# IDC_EXT_Connectors.net
KiCad netlist of a schematic drawn in Altium Designer
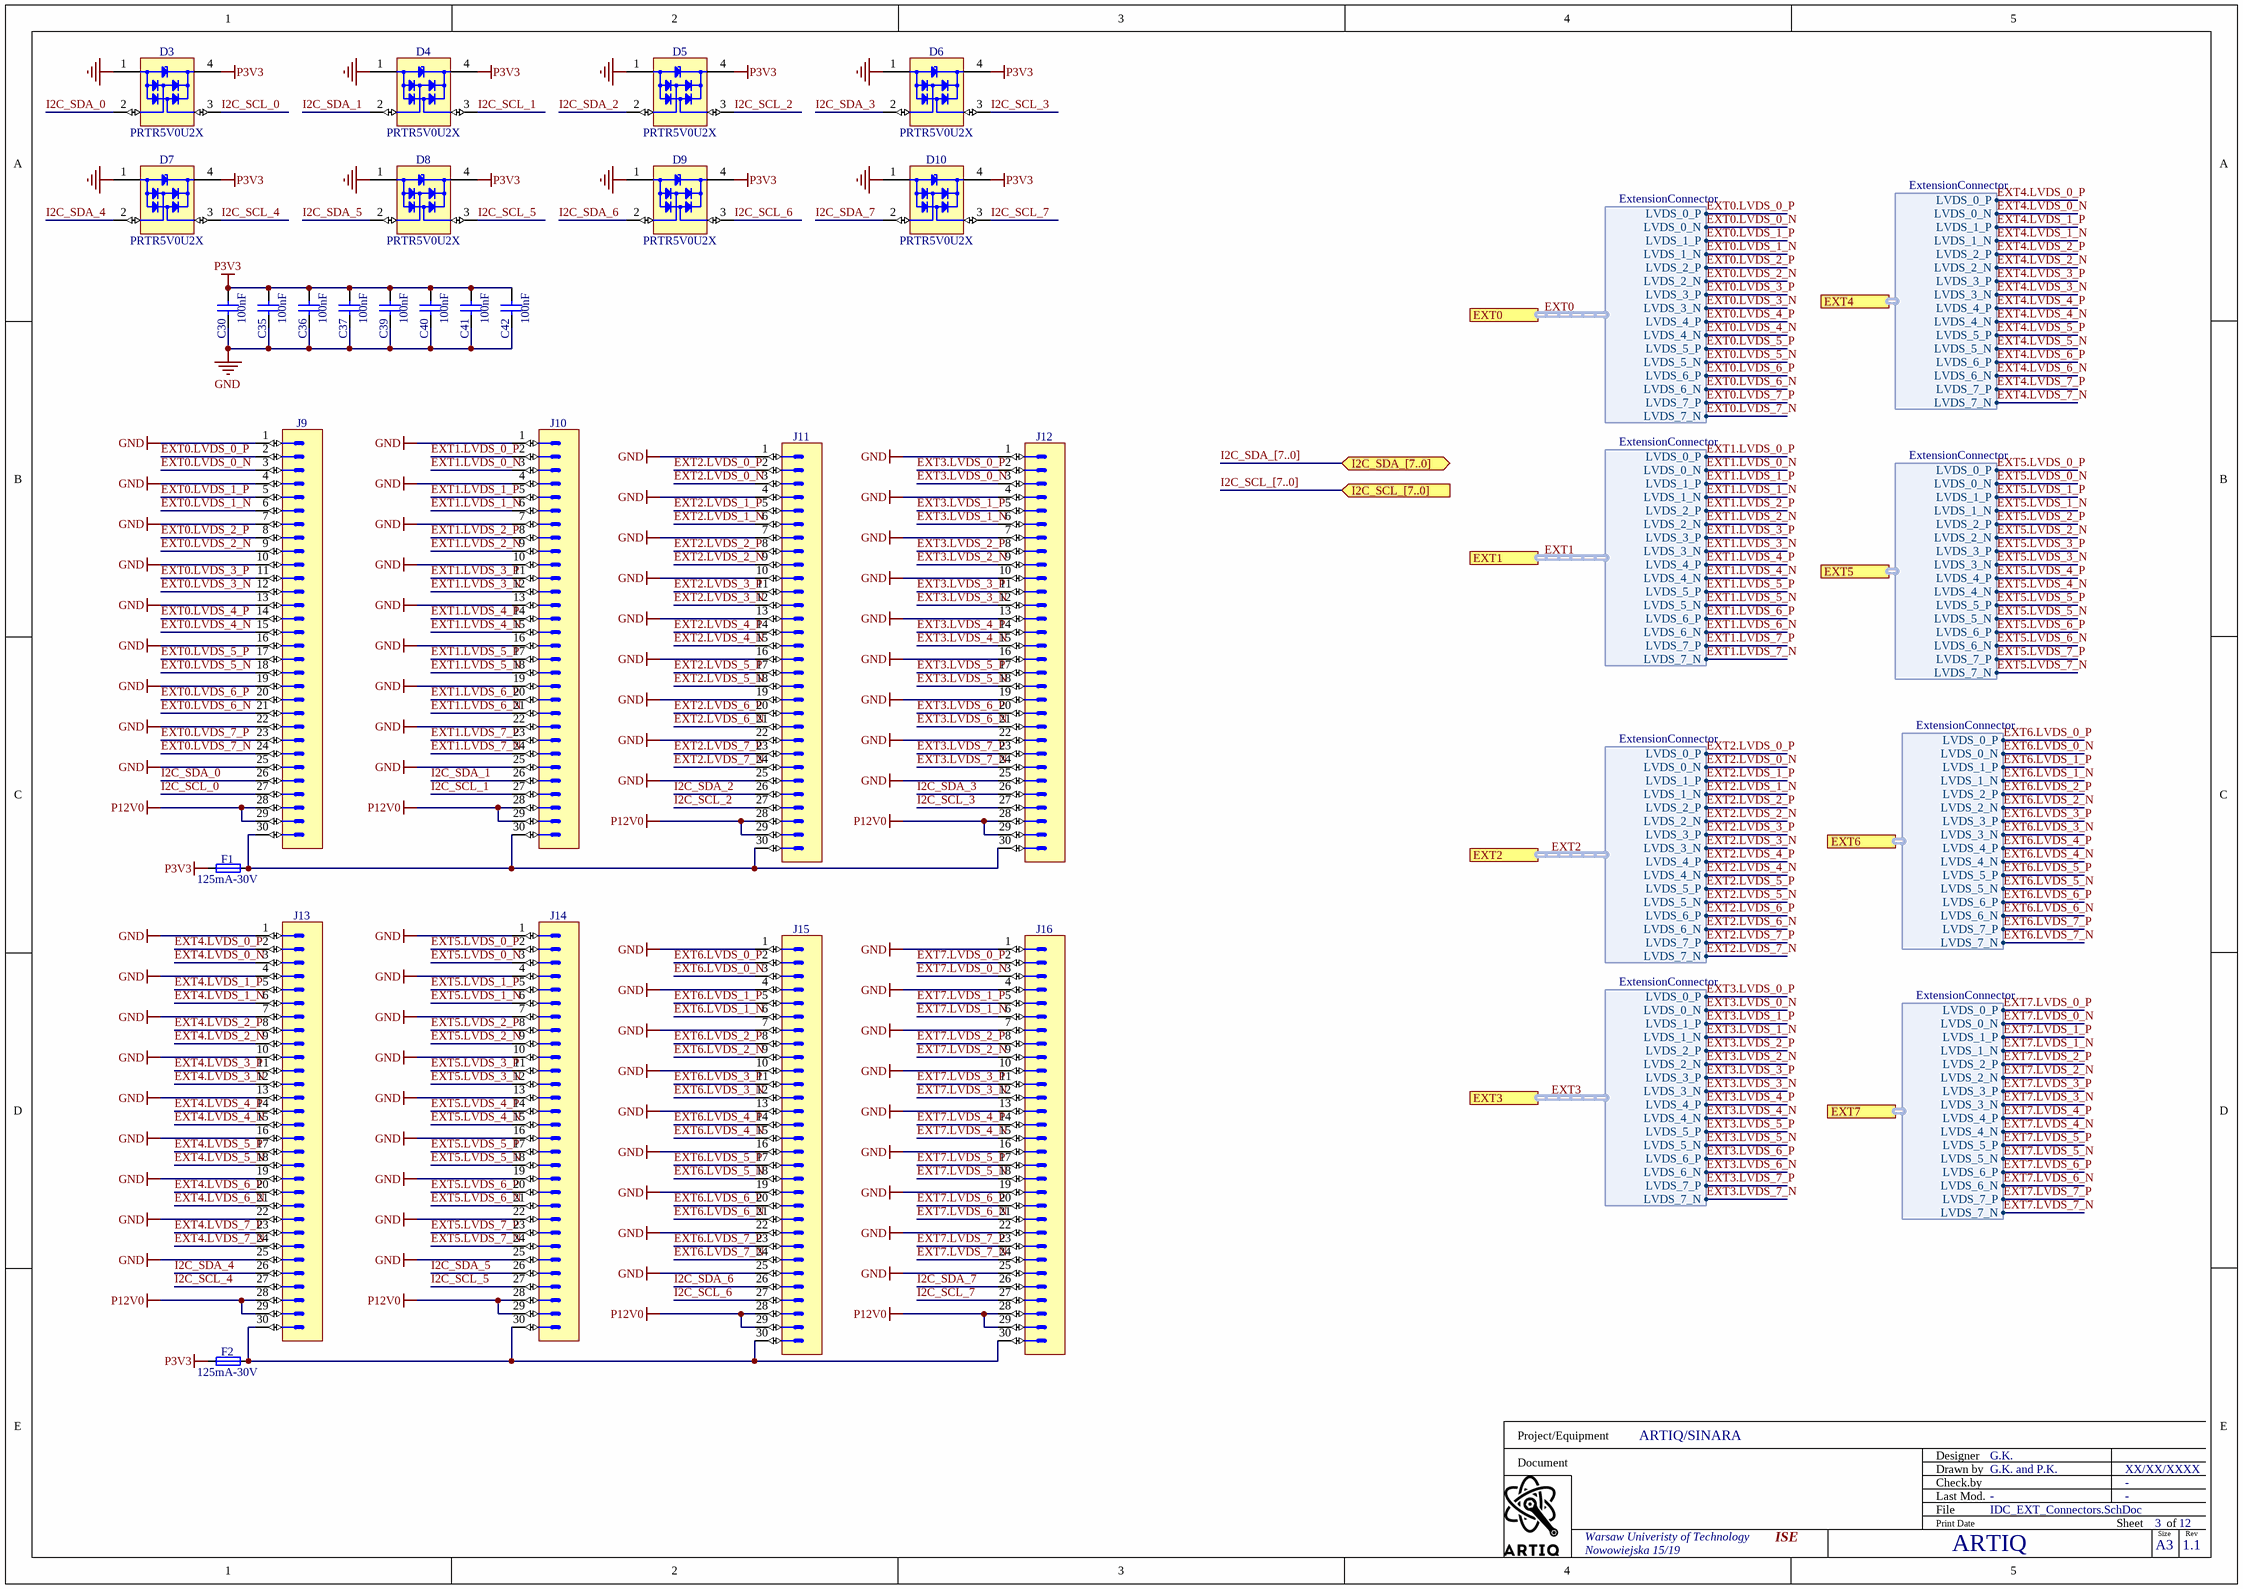
[diagram p0: IDC_EXT_Connectors.SchDoc]

(export (version "E")
  (design (tool "Eeschema 10.0.6"))
  (components
    (comp (ref "C30")
      (value "100nF")
      (footprint "CAPC0603X33N")
      (description "Non-polarised capacitor")
      (fields
        (field (name "PART NUMBER") "CC0201_100NF_6.3V_10%_X5R")
        (field (name "VOLTAGE") "6.3V")
        (field (name "AUTHOR") "CERN DEM JLC")
      )
      (libsource (lib "Capacitors") (part "Capacitor - non polarized"))
    )
    (comp (ref "C35")
      (value "100nF")
      (footprint "CAPC0603X33N")
      (description "Non-polarised capacitor")
      (fields
        (field (name "PART NUMBER") "CC0201_100NF_6.3V_10%_X5R")
        (field (name "VOLTAGE") "6.3V")
        (field (name "AUTHOR") "CERN DEM JLC")
      )
      (libsource (lib "Capacitors") (part "Capacitor - non polarized"))
    )
    (comp (ref "C36")
      (value "100nF")
      (footprint "CAPC0603X33N")
      (description "Non-polarised capacitor")
      (fields
        (field (name "PART NUMBER") "CC0201_100NF_6.3V_10%_X5R")
        (field (name "VOLTAGE") "6.3V")
        (field (name "AUTHOR") "CERN DEM JLC")
      )
      (libsource (lib "Capacitors") (part "Capacitor - non polarized"))
    )
    (comp (ref "C37")
      (value "100nF")
      (footprint "CAPC0603X33N")
      (description "Non-polarised capacitor")
      (fields
        (field (name "PART NUMBER") "CC0201_100NF_6.3V_10%_X5R")
        (field (name "VOLTAGE") "6.3V")
        (field (name "AUTHOR") "CERN DEM JLC")
      )
      (libsource (lib "Capacitors") (part "Capacitor - non polarized"))
    )
    (comp (ref "C39")
      (value "100nF")
      (footprint "CAPC0603X33N")
      (description "Non-polarised capacitor")
      (fields
        (field (name "PART NUMBER") "CC0201_100NF_6.3V_10%_X5R")
        (field (name "VOLTAGE") "6.3V")
        (field (name "AUTHOR") "CERN DEM JLC")
      )
      (libsource (lib "Capacitors") (part "Capacitor - non polarized"))
    )
    (comp (ref "C40")
      (value "100nF")
      (footprint "CAPC0603X33N")
      (description "Non-polarised capacitor")
      (fields
        (field (name "PART NUMBER") "CC0201_100NF_6.3V_10%_X5R")
        (field (name "VOLTAGE") "6.3V")
        (field (name "AUTHOR") "CERN DEM JLC")
      )
      (libsource (lib "Capacitors") (part "Capacitor - non polarized"))
    )
    (comp (ref "C41")
      (value "100nF")
      (footprint "CAPC0603X33N")
      (description "Non-polarised capacitor")
      (fields
        (field (name "PART NUMBER") "CC0201_100NF_6.3V_10%_X5R")
        (field (name "VOLTAGE") "6.3V")
        (field (name "AUTHOR") "CERN DEM JLC")
      )
      (libsource (lib "Capacitors") (part "Capacitor - non polarized"))
    )
    (comp (ref "C42")
      (value "100nF")
      (footprint "CAPC0603X33N")
      (description "Non-polarised capacitor")
      (fields
        (field (name "PART NUMBER") "CC0201_100NF_6.3V_10%_X5R")
        (field (name "VOLTAGE") "6.3V")
        (field (name "AUTHOR") "CERN DEM JLC")
      )
      (libsource (lib "Capacitors") (part "Capacitor - non polarized"))
    )
    (comp (ref "D3")
      (value "PRTR5V0U2X")
      (footprint "SOT190P230X110-4N")
      (description "Ultra Low Capacitance Double Rail-to-Rail ESD Protection Diode")
      (fields
        (field (name "VOLTAGE") "5.5V")
        (field (name "MANUFACTURER") "NXP SEMICONDUCTORS")
        (field (name "AUTHOR") "CERN DEM JLC")
      )
      (libsource (lib "ICs And Semiconductors") (part "PRTR5V0U2X"))
    )
    (comp (ref "D4")
      (value "PRTR5V0U2X")
      (footprint "SOT190P230X110-4N")
      (description "Ultra Low Capacitance Double Rail-to-Rail ESD Protection Diode")
      (fields
        (field (name "VOLTAGE") "5.5V")
        (field (name "MANUFACTURER") "NXP SEMICONDUCTORS")
        (field (name "AUTHOR") "CERN DEM JLC")
      )
      (libsource (lib "ICs And Semiconductors") (part "PRTR5V0U2X"))
    )
    (comp (ref "D5")
      (value "PRTR5V0U2X")
      (footprint "SOT190P230X110-4N")
      (description "Ultra Low Capacitance Double Rail-to-Rail ESD Protection Diode")
      (fields
        (field (name "VOLTAGE") "5.5V")
        (field (name "MANUFACTURER") "NXP SEMICONDUCTORS")
        (field (name "AUTHOR") "CERN DEM JLC")
      )
      (libsource (lib "ICs And Semiconductors") (part "PRTR5V0U2X"))
    )
    (comp (ref "D6")
      (value "PRTR5V0U2X")
      (footprint "SOT190P230X110-4N")
      (description "Ultra Low Capacitance Double Rail-to-Rail ESD Protection Diode")
      (fields
        (field (name "VOLTAGE") "5.5V")
        (field (name "MANUFACTURER") "NXP SEMICONDUCTORS")
        (field (name "AUTHOR") "CERN DEM JLC")
      )
      (libsource (lib "ICs And Semiconductors") (part "PRTR5V0U2X"))
    )
    (comp (ref "D7")
      (value "PRTR5V0U2X")
      (footprint "SOT190P230X110-4N")
      (description "Ultra Low Capacitance Double Rail-to-Rail ESD Protection Diode")
      (fields
        (field (name "VOLTAGE") "5.5V")
        (field (name "MANUFACTURER") "NXP SEMICONDUCTORS")
        (field (name "AUTHOR") "CERN DEM JLC")
      )
      (libsource (lib "ICs And Semiconductors") (part "PRTR5V0U2X"))
    )
    (comp (ref "D8")
      (value "PRTR5V0U2X")
      (footprint "SOT190P230X110-4N")
      (description "Ultra Low Capacitance Double Rail-to-Rail ESD Protection Diode")
      (fields
        (field (name "VOLTAGE") "5.5V")
        (field (name "MANUFACTURER") "NXP SEMICONDUCTORS")
        (field (name "AUTHOR") "CERN DEM JLC")
      )
      (libsource (lib "ICs And Semiconductors") (part "PRTR5V0U2X"))
    )
    (comp (ref "D9")
      (value "PRTR5V0U2X")
      (footprint "SOT190P230X110-4N")
      (description "Ultra Low Capacitance Double Rail-to-Rail ESD Protection Diode")
      (fields
        (field (name "VOLTAGE") "5.5V")
        (field (name "MANUFACTURER") "NXP SEMICONDUCTORS")
        (field (name "AUTHOR") "CERN DEM JLC")
      )
      (libsource (lib "ICs And Semiconductors") (part "PRTR5V0U2X"))
    )
    (comp (ref "D10")
      (value "PRTR5V0U2X")
      (footprint "SOT190P230X110-4N")
      (description "Ultra Low Capacitance Double Rail-to-Rail ESD Protection Diode")
      (fields
        (field (name "VOLTAGE") "5.5V")
        (field (name "MANUFACTURER") "NXP SEMICONDUCTORS")
        (field (name "AUTHOR") "CERN DEM JLC")
      )
      (libsource (lib "ICs And Semiconductors") (part "PRTR5V0U2X"))
    )
    (comp (ref "F1")
      (value "125mA-30V")
      (footprint "FUSR_LITTELFUSE_1206L012")
      (description "Fuse")
      (fields
        (field (name "PART NUMBER") "FUSR_LITTELFUSE_1206L012")
        (field (name "MANUFACTURER") "LITTELFUSE")
        (field (name "AUTHOR") "CERN DEM JLC")
      )
      (libsource (lib "Eletro-mechanical") (part "Fuse"))
    )
    (comp (ref "F2")
      (value "125mA-30V")
      (footprint "FUSR_LITTELFUSE_1206L012")
      (description "Fuse")
      (fields
        (field (name "PART NUMBER") "FUSR_LITTELFUSE_1206L012")
        (field (name "MANUFACTURER") "LITTELFUSE")
        (field (name "AUTHOR") "CERN DEM JLC")
      )
      (libsource (lib "Eletro-mechanical") (part "Fuse"))
    )
    (comp (ref "J9")
      (value "~")
      (footprint "3M_N2530-6002RB")
      (description "Connector 30 Male")
      (fields
        (field (name "PART NUMBER") "3M_N2530-6002RB")
        (field (name "MANUFACTURER") "3M")
        (field (name "AUTHOR") "CERN DEM JLC")
      )
      (libsource (lib "Connectors") (part "Connector 30 Male"))
    )
    (comp (ref "J10")
      (value "~")
      (footprint "3M_N2530-6002RB")
      (description "Connector 30 Male")
      (fields
        (field (name "PART NUMBER") "3M_N2530-6002RB")
        (field (name "MANUFACTURER") "3M")
        (field (name "AUTHOR") "CERN DEM JLC")
      )
      (libsource (lib "Connectors") (part "Connector 30 Male"))
    )
    (comp (ref "J11")
      (value "~")
      (footprint "3M_N2530-6002RB")
      (description "Connector 30 Male")
      (fields
        (field (name "PART NUMBER") "3M_N2530-6002RB")
        (field (name "MANUFACTURER") "3M")
        (field (name "AUTHOR") "CERN DEM JLC")
      )
      (libsource (lib "Connectors") (part "Connector 30 Male"))
    )
    (comp (ref "J12")
      (value "~")
      (footprint "3M_N2530-6002RB")
      (description "Connector 30 Male")
      (fields
        (field (name "PART NUMBER") "3M_N2530-6002RB")
        (field (name "MANUFACTURER") "3M")
        (field (name "AUTHOR") "CERN DEM JLC")
      )
      (libsource (lib "Connectors") (part "Connector 30 Male"))
    )
    (comp (ref "J13")
      (value "~")
      (footprint "3M_N2530-6002RB")
      (description "Connector 30 Male")
      (fields
        (field (name "PART NUMBER") "3M_N2530-6002RB")
        (field (name "MANUFACTURER") "3M")
        (field (name "AUTHOR") "CERN DEM JLC")
      )
      (libsource (lib "Connectors") (part "Connector 30 Male"))
    )
    (comp (ref "J14")
      (value "~")
      (footprint "3M_N2530-6002RB")
      (description "Connector 30 Male")
      (fields
        (field (name "PART NUMBER") "3M_N2530-6002RB")
        (field (name "MANUFACTURER") "3M")
        (field (name "AUTHOR") "CERN DEM JLC")
      )
      (libsource (lib "Connectors") (part "Connector 30 Male"))
    )
    (comp (ref "J15")
      (value "~")
      (footprint "3M_N2530-6002RB")
      (description "Connector 30 Male")
      (fields
        (field (name "PART NUMBER") "3M_N2530-6002RB")
        (field (name "MANUFACTURER") "3M")
        (field (name "AUTHOR") "CERN DEM JLC")
      )
      (libsource (lib "Connectors") (part "Connector 30 Male"))
    )
    (comp (ref "J16")
      (value "~")
      (footprint "3M_N2530-6002RB")
      (description "Connector 30 Male")
      (fields
        (field (name "PART NUMBER") "3M_N2530-6002RB")
        (field (name "MANUFACTURER") "3M")
        (field (name "AUTHOR") "CERN DEM JLC")
      )
      (libsource (lib "Connectors") (part "Connector 30 Male"))
    )
  )
  (nets
    (net (code "6") (name "/EXT0.LVDS_0_N") (class "Default")
      (node (ref "J9") (pin "3") (pinfunction "3_3") (pintype "bidirectional"))
    )
    (net (code "7") (name "/EXT0.LVDS_0_P") (class "Default")
      (node (ref "J9") (pin "2") (pinfunction "2_2") (pintype "bidirectional"))
    )
    (net (code "8") (name "/EXT0.LVDS_1_N") (class "Default")
      (node (ref "J9") (pin "6") (pinfunction "6_6") (pintype "bidirectional"))
    )
    (net (code "9") (name "/EXT0.LVDS_1_P") (class "Default")
      (node (ref "J9") (pin "5") (pinfunction "5_5") (pintype "bidirectional"))
    )
    (net (code "10") (name "/EXT0.LVDS_2_N") (class "Default")
      (node (ref "J9") (pin "9") (pinfunction "9_9") (pintype "bidirectional"))
    )
    (net (code "11") (name "/EXT0.LVDS_2_P") (class "Default")
      (node (ref "J9") (pin "8") (pinfunction "8_8") (pintype "bidirectional"))
    )
    (net (code "12") (name "/EXT0.LVDS_3_N") (class "Default")
      (node (ref "J9") (pin "12") (pinfunction "12_12") (pintype "bidirectional"))
    )
    (net (code "13") (name "/EXT0.LVDS_3_P") (class "Default")
      (node (ref "J9") (pin "11") (pinfunction "11_11") (pintype "bidirectional"))
    )
    (net (code "14") (name "/EXT0.LVDS_4_N") (class "Default")
      (node (ref "J9") (pin "15") (pinfunction "15_15") (pintype "bidirectional"))
    )
    (net (code "15") (name "/EXT0.LVDS_4_P") (class "Default")
      (node (ref "J9") (pin "14") (pinfunction "14_14") (pintype "bidirectional"))
    )
    (net (code "16") (name "/EXT0.LVDS_5_N") (class "Default")
      (node (ref "J9") (pin "18") (pinfunction "18_18") (pintype "bidirectional"))
    )
    (net (code "17") (name "/EXT0.LVDS_5_P") (class "Default")
      (node (ref "J9") (pin "17") (pinfunction "17_17") (pintype "bidirectional"))
    )
    (net (code "18") (name "/EXT0.LVDS_6_N") (class "Default")
      (node (ref "J9") (pin "21") (pinfunction "21_21") (pintype "bidirectional"))
    )
    (net (code "19") (name "/EXT0.LVDS_6_P") (class "Default")
      (node (ref "J9") (pin "20") (pinfunction "20_20") (pintype "bidirectional"))
    )
    (net (code "20") (name "/EXT0.LVDS_7_N") (class "Default")
      (node (ref "J9") (pin "24") (pinfunction "24_24") (pintype "bidirectional"))
    )
    (net (code "21") (name "/EXT0.LVDS_7_P") (class "Default")
      (node (ref "J9") (pin "23") (pinfunction "23_23") (pintype "bidirectional"))
    )
    (net (code "23") (name "/EXT1.LVDS_0_N") (class "Default")
      (node (ref "J10") (pin "3") (pinfunction "3_3") (pintype "bidirectional"))
    )
    (net (code "24") (name "/EXT1.LVDS_0_P") (class "Default")
      (node (ref "J10") (pin "2") (pinfunction "2_2") (pintype "bidirectional"))
    )
    (net (code "25") (name "/EXT1.LVDS_1_N") (class "Default")
      (node (ref "J10") (pin "6") (pinfunction "6_6") (pintype "bidirectional"))
    )
    (net (code "26") (name "/EXT1.LVDS_1_P") (class "Default")
      (node (ref "J10") (pin "5") (pinfunction "5_5") (pintype "bidirectional"))
    )
    (net (code "27") (name "/EXT1.LVDS_2_N") (class "Default")
      (node (ref "J10") (pin "9") (pinfunction "9_9") (pintype "bidirectional"))
    )
    (net (code "28") (name "/EXT1.LVDS_2_P") (class "Default")
      (node (ref "J10") (pin "8") (pinfunction "8_8") (pintype "bidirectional"))
    )
    (net (code "29") (name "/EXT1.LVDS_3_N") (class "Default")
      (node (ref "J10") (pin "12") (pinfunction "12_12") (pintype "bidirectional"))
    )
    (net (code "30") (name "/EXT1.LVDS_3_P") (class "Default")
      (node (ref "J10") (pin "11") (pinfunction "11_11") (pintype "bidirectional"))
    )
    (net (code "31") (name "/EXT1.LVDS_4_N") (class "Default")
      (node (ref "J10") (pin "15") (pinfunction "15_15") (pintype "bidirectional"))
    )
    (net (code "32") (name "/EXT1.LVDS_4_P") (class "Default")
      (node (ref "J10") (pin "14") (pinfunction "14_14") (pintype "bidirectional"))
    )
    (net (code "33") (name "/EXT1.LVDS_5_N") (class "Default")
      (node (ref "J10") (pin "18") (pinfunction "18_18") (pintype "bidirectional"))
    )
    (net (code "34") (name "/EXT1.LVDS_5_P") (class "Default")
      (node (ref "J10") (pin "17") (pinfunction "17_17") (pintype "bidirectional"))
    )
    (net (code "35") (name "/EXT1.LVDS_6_N") (class "Default")
      (node (ref "J10") (pin "21") (pinfunction "21_21") (pintype "bidirectional"))
    )
    (net (code "36") (name "/EXT1.LVDS_6_P") (class "Default")
      (node (ref "J10") (pin "20") (pinfunction "20_20") (pintype "bidirectional"))
    )
    (net (code "37") (name "/EXT1.LVDS_7_N") (class "Default")
      (node (ref "J10") (pin "24") (pinfunction "24_24") (pintype "bidirectional"))
    )
    (net (code "38") (name "/EXT1.LVDS_7_P") (class "Default")
      (node (ref "J10") (pin "23") (pinfunction "23_23") (pintype "bidirectional"))
    )
    (net (code "40") (name "/EXT2.LVDS_0_N") (class "Default")
      (node (ref "J11") (pin "3") (pinfunction "3_3") (pintype "bidirectional"))
    )
    (net (code "41") (name "/EXT2.LVDS_0_P") (class "Default")
      (node (ref "J11") (pin "2") (pinfunction "2_2") (pintype "bidirectional"))
    )
    (net (code "42") (name "/EXT2.LVDS_1_N") (class "Default")
      (node (ref "J11") (pin "6") (pinfunction "6_6") (pintype "bidirectional"))
    )
    (net (code "43") (name "/EXT2.LVDS_1_P") (class "Default")
      (node (ref "J11") (pin "5") (pinfunction "5_5") (pintype "bidirectional"))
    )
    (net (code "44") (name "/EXT2.LVDS_2_N") (class "Default")
      (node (ref "J11") (pin "9") (pinfunction "9_9") (pintype "bidirectional"))
    )
    (net (code "45") (name "/EXT2.LVDS_2_P") (class "Default")
      (node (ref "J11") (pin "8") (pinfunction "8_8") (pintype "bidirectional"))
    )
    (net (code "46") (name "/EXT2.LVDS_3_N") (class "Default")
      (node (ref "J11") (pin "12") (pinfunction "12_12") (pintype "bidirectional"))
    )
    (net (code "47") (name "/EXT2.LVDS_3_P") (class "Default")
      (node (ref "J11") (pin "11") (pinfunction "11_11") (pintype "bidirectional"))
    )
    (net (code "48") (name "/EXT2.LVDS_4_N") (class "Default")
      (node (ref "J11") (pin "15") (pinfunction "15_15") (pintype "bidirectional"))
    )
    (net (code "49") (name "/EXT2.LVDS_4_P") (class "Default")
      (node (ref "J11") (pin "14") (pinfunction "14_14") (pintype "bidirectional"))
    )
    (net (code "50") (name "/EXT2.LVDS_5_N") (class "Default")
      (node (ref "J11") (pin "18") (pinfunction "18_18") (pintype "bidirectional"))
    )
    (net (code "51") (name "/EXT2.LVDS_5_P") (class "Default")
      (node (ref "J11") (pin "17") (pinfunction "17_17") (pintype "bidirectional"))
    )
    (net (code "52") (name "/EXT2.LVDS_6_N") (class "Default")
      (node (ref "J11") (pin "21") (pinfunction "21_21") (pintype "bidirectional"))
    )
    (net (code "53") (name "/EXT2.LVDS_6_P") (class "Default")
      (node (ref "J11") (pin "20") (pinfunction "20_20") (pintype "bidirectional"))
    )
    (net (code "54") (name "/EXT2.LVDS_7_N") (class "Default")
      (node (ref "J11") (pin "24") (pinfunction "24_24") (pintype "bidirectional"))
    )
    (net (code "55") (name "/EXT2.LVDS_7_P") (class "Default")
      (node (ref "J11") (pin "23") (pinfunction "23_23") (pintype "bidirectional"))
    )
    (net (code "57") (name "/EXT3.LVDS_0_N") (class "Default")
      (node (ref "J12") (pin "3") (pinfunction "3_3") (pintype "bidirectional"))
    )
    (net (code "58") (name "/EXT3.LVDS_0_P") (class "Default")
      (node (ref "J12") (pin "2") (pinfunction "2_2") (pintype "bidirectional"))
    )
    (net (code "59") (name "/EXT3.LVDS_1_N") (class "Default")
      (node (ref "J12") (pin "6") (pinfunction "6_6") (pintype "bidirectional"))
    )
    (net (code "60") (name "/EXT3.LVDS_1_P") (class "Default")
      (node (ref "J12") (pin "5") (pinfunction "5_5") (pintype "bidirectional"))
    )
    (net (code "61") (name "/EXT3.LVDS_2_N") (class "Default")
      (node (ref "J12") (pin "9") (pinfunction "9_9") (pintype "bidirectional"))
    )
    (net (code "62") (name "/EXT3.LVDS_2_P") (class "Default")
      (node (ref "J12") (pin "8") (pinfunction "8_8") (pintype "bidirectional"))
    )
    (net (code "63") (name "/EXT3.LVDS_3_N") (class "Default")
      (node (ref "J12") (pin "12") (pinfunction "12_12") (pintype "bidirectional"))
    )
    (net (code "64") (name "/EXT3.LVDS_3_P") (class "Default")
      (node (ref "J12") (pin "11") (pinfunction "11_11") (pintype "bidirectional"))
    )
    (net (code "65") (name "/EXT3.LVDS_4_N") (class "Default")
      (node (ref "J12") (pin "15") (pinfunction "15_15") (pintype "bidirectional"))
    )
    (net (code "66") (name "/EXT3.LVDS_4_P") (class "Default")
      (node (ref "J12") (pin "14") (pinfunction "14_14") (pintype "bidirectional"))
    )
    (net (code "67") (name "/EXT3.LVDS_5_N") (class "Default")
      (node (ref "J12") (pin "18") (pinfunction "18_18") (pintype "bidirectional"))
    )
    (net (code "68") (name "/EXT3.LVDS_5_P") (class "Default")
      (node (ref "J12") (pin "17") (pinfunction "17_17") (pintype "bidirectional"))
    )
    (net (code "69") (name "/EXT3.LVDS_6_N") (class "Default")
      (node (ref "J12") (pin "21") (pinfunction "21_21") (pintype "bidirectional"))
    )
    (net (code "70") (name "/EXT3.LVDS_6_P") (class "Default")
      (node (ref "J12") (pin "20") (pinfunction "20_20") (pintype "bidirectional"))
    )
    (net (code "71") (name "/EXT3.LVDS_7_N") (class "Default")
      (node (ref "J12") (pin "24") (pinfunction "24_24") (pintype "bidirectional"))
    )
    (net (code "72") (name "/EXT3.LVDS_7_P") (class "Default")
      (node (ref "J12") (pin "23") (pinfunction "23_23") (pintype "bidirectional"))
    )
    (net (code "74") (name "/EXT4.LVDS_0_N") (class "Default")
      (node (ref "J13") (pin "3") (pinfunction "3_3") (pintype "bidirectional"))
    )
    (net (code "75") (name "/EXT4.LVDS_0_P") (class "Default")
      (node (ref "J13") (pin "2") (pinfunction "2_2") (pintype "bidirectional"))
    )
    (net (code "76") (name "/EXT4.LVDS_1_N") (class "Default")
      (node (ref "J13") (pin "6") (pinfunction "6_6") (pintype "bidirectional"))
    )
    (net (code "77") (name "/EXT4.LVDS_1_P") (class "Default")
      (node (ref "J13") (pin "5") (pinfunction "5_5") (pintype "bidirectional"))
    )
    (net (code "78") (name "/EXT4.LVDS_2_N") (class "Default")
      (node (ref "J13") (pin "9") (pinfunction "9_9") (pintype "bidirectional"))
    )
    (net (code "79") (name "/EXT4.LVDS_2_P") (class "Default")
      (node (ref "J13") (pin "8") (pinfunction "8_8") (pintype "bidirectional"))
    )
    (net (code "80") (name "/EXT4.LVDS_3_N") (class "Default")
      (node (ref "J13") (pin "12") (pinfunction "12_12") (pintype "bidirectional"))
    )
    (net (code "81") (name "/EXT4.LVDS_3_P") (class "Default")
      (node (ref "J13") (pin "11") (pinfunction "11_11") (pintype "bidirectional"))
    )
    (net (code "82") (name "/EXT4.LVDS_4_N") (class "Default")
      (node (ref "J13") (pin "15") (pinfunction "15_15") (pintype "bidirectional"))
    )
    (net (code "83") (name "/EXT4.LVDS_4_P") (class "Default")
      (node (ref "J13") (pin "14") (pinfunction "14_14") (pintype "bidirectional"))
    )
    (net (code "84") (name "/EXT4.LVDS_5_N") (class "Default")
      (node (ref "J13") (pin "18") (pinfunction "18_18") (pintype "bidirectional"))
    )
    (net (code "85") (name "/EXT4.LVDS_5_P") (class "Default")
      (node (ref "J13") (pin "17") (pinfunction "17_17") (pintype "bidirectional"))
    )
    (net (code "86") (name "/EXT4.LVDS_6_N") (class "Default")
      (node (ref "J13") (pin "21") (pinfunction "21_21") (pintype "bidirectional"))
    )
    (net (code "87") (name "/EXT4.LVDS_6_P") (class "Default")
      (node (ref "J13") (pin "20") (pinfunction "20_20") (pintype "bidirectional"))
    )
    (net (code "88") (name "/EXT4.LVDS_7_N") (class "Default")
      (node (ref "J13") (pin "24") (pinfunction "24_24") (pintype "bidirectional"))
    )
    (net (code "89") (name "/EXT4.LVDS_7_P") (class "Default")
      (node (ref "J13") (pin "23") (pinfunction "23_23") (pintype "bidirectional"))
    )
    (net (code "90") (name "/EXT5.LVDS_0_N") (class "Default")
      (node (ref "J14") (pin "3") (pinfunction "3_3") (pintype "bidirectional"))
    )
    (net (code "91") (name "/EXT5.LVDS_0_P") (class "Default")
      (node (ref "J14") (pin "2") (pinfunction "2_2") (pintype "bidirectional"))
    )
    (net (code "92") (name "/EXT5.LVDS_1_N") (class "Default")
      (node (ref "J14") (pin "6") (pinfunction "6_6") (pintype "bidirectional"))
    )
    (net (code "93") (name "/EXT5.LVDS_1_P") (class "Default")
      (node (ref "J14") (pin "5") (pinfunction "5_5") (pintype "bidirectional"))
    )
    (net (code "94") (name "/EXT5.LVDS_2_N") (class "Default")
      (node (ref "J14") (pin "9") (pinfunction "9_9") (pintype "bidirectional"))
    )
    (net (code "95") (name "/EXT5.LVDS_2_P") (class "Default")
      (node (ref "J14") (pin "8") (pinfunction "8_8") (pintype "bidirectional"))
    )
    (net (code "96") (name "/EXT5.LVDS_3_N") (class "Default")
      (node (ref "J14") (pin "12") (pinfunction "12_12") (pintype "bidirectional"))
    )
    (net (code "97") (name "/EXT5.LVDS_3_P") (class "Default")
      (node (ref "J14") (pin "11") (pinfunction "11_11") (pintype "bidirectional"))
    )
    (net (code "98") (name "/EXT5.LVDS_4_N") (class "Default")
      (node (ref "J14") (pin "15") (pinfunction "15_15") (pintype "bidirectional"))
    )
    (net (code "99") (name "/EXT5.LVDS_4_P") (class "Default")
      (node (ref "J14") (pin "14") (pinfunction "14_14") (pintype "bidirectional"))
    )
    (net (code "100") (name "/EXT5.LVDS_5_N") (class "Default")
      (node (ref "J14") (pin "18") (pinfunction "18_18") (pintype "bidirectional"))
    )
    (net (code "101") (name "/EXT5.LVDS_5_P") (class "Default")
      (node (ref "J14") (pin "17") (pinfunction "17_17") (pintype "bidirectional"))
    )
    (net (code "102") (name "/EXT5.LVDS_6_N") (class "Default")
      (node (ref "J14") (pin "21") (pinfunction "21_21") (pintype "bidirectional"))
    )
    (net (code "103") (name "/EXT5.LVDS_6_P") (class "Default")
      (node (ref "J14") (pin "20") (pinfunction "20_20") (pintype "bidirectional"))
    )
    (net (code "104") (name "/EXT5.LVDS_7_N") (class "Default")
      (node (ref "J14") (pin "24") (pinfunction "24_24") (pintype "bidirectional"))
    )
    (net (code "105") (name "/EXT5.LVDS_7_P") (class "Default")
      (node (ref "J14") (pin "23") (pinfunction "23_23") (pintype "bidirectional"))
    )
    (net (code "106") (name "/EXT6.LVDS_0_N") (class "Default")
      (node (ref "J15") (pin "3") (pinfunction "3_3") (pintype "bidirectional"))
    )
    (net (code "107") (name "/EXT6.LVDS_0_P") (class "Default")
      (node (ref "J15") (pin "2") (pinfunction "2_2") (pintype "bidirectional"))
    )
    (net (code "108") (name "/EXT6.LVDS_1_N") (class "Default")
      (node (ref "J15") (pin "6") (pinfunction "6_6") (pintype "bidirectional"))
    )
    (net (code "109") (name "/EXT6.LVDS_1_P") (class "Default")
      (node (ref "J15") (pin "5") (pinfunction "5_5") (pintype "bidirectional"))
    )
    (net (code "110") (name "/EXT6.LVDS_2_N") (class "Default")
      (node (ref "J15") (pin "9") (pinfunction "9_9") (pintype "bidirectional"))
    )
    (net (code "111") (name "/EXT6.LVDS_2_P") (class "Default")
      (node (ref "J15") (pin "8") (pinfunction "8_8") (pintype "bidirectional"))
    )
    (net (code "112") (name "/EXT6.LVDS_3_N") (class "Default")
      (node (ref "J15") (pin "12") (pinfunction "12_12") (pintype "bidirectional"))
    )
    (net (code "113") (name "/EXT6.LVDS_3_P") (class "Default")
      (node (ref "J15") (pin "11") (pinfunction "11_11") (pintype "bidirectional"))
    )
    (net (code "114") (name "/EXT6.LVDS_4_N") (class "Default")
      (node (ref "J15") (pin "15") (pinfunction "15_15") (pintype "bidirectional"))
    )
    (net (code "115") (name "/EXT6.LVDS_4_P") (class "Default")
      (node (ref "J15") (pin "14") (pinfunction "14_14") (pintype "bidirectional"))
    )
    (net (code "116") (name "/EXT6.LVDS_5_N") (class "Default")
      (node (ref "J15") (pin "18") (pinfunction "18_18") (pintype "bidirectional"))
    )
    (net (code "117") (name "/EXT6.LVDS_5_P") (class "Default")
      (node (ref "J15") (pin "17") (pinfunction "17_17") (pintype "bidirectional"))
    )
    (net (code "118") (name "/EXT6.LVDS_6_N") (class "Default")
      (node (ref "J15") (pin "21") (pinfunction "21_21") (pintype "bidirectional"))
    )
    (net (code "119") (name "/EXT6.LVDS_6_P") (class "Default")
      (node (ref "J15") (pin "20") (pinfunction "20_20") (pintype "bidirectional"))
    )
    (net (code "120") (name "/EXT6.LVDS_7_N") (class "Default")
      (node (ref "J15") (pin "24") (pinfunction "24_24") (pintype "bidirectional"))
    )
    (net (code "121") (name "/EXT6.LVDS_7_P") (class "Default")
      (node (ref "J15") (pin "23") (pinfunction "23_23") (pintype "bidirectional"))
    )
    (net (code "122") (name "/EXT7.LVDS_0_N") (class "Default")
      (node (ref "J16") (pin "3") (pinfunction "3_3") (pintype "bidirectional"))
    )
    (net (code "123") (name "/EXT7.LVDS_0_P") (class "Default")
      (node (ref "J16") (pin "2") (pinfunction "2_2") (pintype "bidirectional"))
    )
    (net (code "124") (name "/EXT7.LVDS_1_N") (class "Default")
      (node (ref "J16") (pin "6") (pinfunction "6_6") (pintype "bidirectional"))
    )
    (net (code "125") (name "/EXT7.LVDS_1_P") (class "Default")
      (node (ref "J16") (pin "5") (pinfunction "5_5") (pintype "bidirectional"))
    )
    (net (code "126") (name "/EXT7.LVDS_2_N") (class "Default")
      (node (ref "J16") (pin "9") (pinfunction "9_9") (pintype "bidirectional"))
    )
    (net (code "127") (name "/EXT7.LVDS_2_P") (class "Default")
      (node (ref "J16") (pin "8") (pinfunction "8_8") (pintype "bidirectional"))
    )
    (net (code "128") (name "/EXT7.LVDS_3_N") (class "Default")
      (node (ref "J16") (pin "12") (pinfunction "12_12") (pintype "bidirectional"))
    )
    (net (code "129") (name "/EXT7.LVDS_3_P") (class "Default")
      (node (ref "J16") (pin "11") (pinfunction "11_11") (pintype "bidirectional"))
    )
    (net (code "130") (name "/EXT7.LVDS_4_N") (class "Default")
      (node (ref "J16") (pin "15") (pinfunction "15_15") (pintype "bidirectional"))
    )
    (net (code "131") (name "/EXT7.LVDS_4_P") (class "Default")
      (node (ref "J16") (pin "14") (pinfunction "14_14") (pintype "bidirectional"))
    )
    (net (code "132") (name "/EXT7.LVDS_5_N") (class "Default")
      (node (ref "J16") (pin "18") (pinfunction "18_18") (pintype "bidirectional"))
    )
    (net (code "133") (name "/EXT7.LVDS_5_P") (class "Default")
      (node (ref "J16") (pin "17") (pinfunction "17_17") (pintype "bidirectional"))
    )
    (net (code "134") (name "/EXT7.LVDS_6_N") (class "Default")
      (node (ref "J16") (pin "21") (pinfunction "21_21") (pintype "bidirectional"))
    )
    (net (code "135") (name "/EXT7.LVDS_6_P") (class "Default")
      (node (ref "J16") (pin "20") (pinfunction "20_20") (pintype "bidirectional"))
    )
    (net (code "136") (name "/EXT7.LVDS_7_N") (class "Default")
      (node (ref "J16") (pin "24") (pinfunction "24_24") (pintype "bidirectional"))
    )
    (net (code "137") (name "/EXT7.LVDS_7_P") (class "Default")
      (node (ref "J16") (pin "23") (pinfunction "23_23") (pintype "bidirectional"))
    )
    (net (code "138") (name "/I2C_SCL_0") (class "Default")
      (node (ref "D3") (pin "3") (pinfunction "I/O2_3") (pintype "bidirectional"))
      (node (ref "J9") (pin "27") (pinfunction "27_27") (pintype "bidirectional"))
    )
    (net (code "139") (name "/I2C_SCL_1") (class "Default")
      (node (ref "D4") (pin "3") (pinfunction "I/O2_3") (pintype "bidirectional"))
      (node (ref "J10") (pin "27") (pinfunction "27_27") (pintype "bidirectional"))
    )
    (net (code "140") (name "/I2C_SCL_2") (class "Default")
      (node (ref "D5") (pin "3") (pinfunction "I/O2_3") (pintype "bidirectional"))
      (node (ref "J11") (pin "27") (pinfunction "27_27") (pintype "bidirectional"))
    )
    (net (code "141") (name "/I2C_SCL_3") (class "Default")
      (node (ref "D6") (pin "3") (pinfunction "I/O2_3") (pintype "bidirectional"))
      (node (ref "J12") (pin "27") (pinfunction "27_27") (pintype "bidirectional"))
    )
    (net (code "142") (name "/I2C_SCL_4") (class "Default")
      (node (ref "D7") (pin "3") (pinfunction "I/O2_3") (pintype "bidirectional"))
      (node (ref "J13") (pin "27") (pinfunction "27_27") (pintype "bidirectional"))
    )
    (net (code "143") (name "/I2C_SCL_5") (class "Default")
      (node (ref "D8") (pin "3") (pinfunction "I/O2_3") (pintype "bidirectional"))
      (node (ref "J14") (pin "27") (pinfunction "27_27") (pintype "bidirectional"))
    )
    (net (code "144") (name "/I2C_SCL_6") (class "Default")
      (node (ref "D9") (pin "3") (pinfunction "I/O2_3") (pintype "bidirectional"))
      (node (ref "J15") (pin "27") (pinfunction "27_27") (pintype "bidirectional"))
    )
    (net (code "145") (name "/I2C_SCL_7") (class "Default")
      (node (ref "D10") (pin "3") (pinfunction "I/O2_3") (pintype "bidirectional"))
      (node (ref "J16") (pin "27") (pinfunction "27_27") (pintype "bidirectional"))
    )
    (net (code "147") (name "/I2C_SDA_0") (class "Default")
      (node (ref "D3") (pin "2") (pinfunction "I/O1_2") (pintype "bidirectional"))
      (node (ref "J9") (pin "26") (pinfunction "26_26") (pintype "bidirectional"))
    )
    (net (code "148") (name "/I2C_SDA_1") (class "Default")
      (node (ref "D4") (pin "2") (pinfunction "I/O1_2") (pintype "bidirectional"))
      (node (ref "J10") (pin "26") (pinfunction "26_26") (pintype "bidirectional"))
    )
    (net (code "149") (name "/I2C_SDA_2") (class "Default")
      (node (ref "D5") (pin "2") (pinfunction "I/O1_2") (pintype "bidirectional"))
      (node (ref "J11") (pin "26") (pinfunction "26_26") (pintype "bidirectional"))
    )
    (net (code "150") (name "/I2C_SDA_3") (class "Default")
      (node (ref "D6") (pin "2") (pinfunction "I/O1_2") (pintype "bidirectional"))
      (node (ref "J12") (pin "26") (pinfunction "26_26") (pintype "bidirectional"))
    )
    (net (code "151") (name "/I2C_SDA_4") (class "Default")
      (node (ref "D7") (pin "2") (pinfunction "I/O1_2") (pintype "bidirectional"))
      (node (ref "J13") (pin "26") (pinfunction "26_26") (pintype "bidirectional"))
    )
    (net (code "152") (name "/I2C_SDA_5") (class "Default")
      (node (ref "D8") (pin "2") (pinfunction "I/O1_2") (pintype "bidirectional"))
      (node (ref "J14") (pin "26") (pinfunction "26_26") (pintype "bidirectional"))
    )
    (net (code "153") (name "/I2C_SDA_6") (class "Default")
      (node (ref "D9") (pin "2") (pinfunction "I/O1_2") (pintype "bidirectional"))
      (node (ref "J15") (pin "26") (pinfunction "26_26") (pintype "bidirectional"))
    )
    (net (code "154") (name "/I2C_SDA_7") (class "Default")
      (node (ref "D10") (pin "2") (pinfunction "I/O1_2") (pintype "bidirectional"))
      (node (ref "J16") (pin "26") (pinfunction "26_26") (pintype "bidirectional"))
    )
    (net (code "157") (name "GND") (class "Default")
      (node (ref "C30") (pin "1") (pinfunction "1_1") (pintype "passive"))
      (node (ref "C35") (pin "1") (pinfunction "1_1") (pintype "passive"))
      (node (ref "C36") (pin "1") (pinfunction "1_1") (pintype "passive"))
      (node (ref "C37") (pin "1") (pinfunction "1_1") (pintype "passive"))
      (node (ref "C39") (pin "1") (pinfunction "1_1") (pintype "passive"))
      (node (ref "C40") (pin "1") (pinfunction "1_1") (pintype "passive"))
      (node (ref "C41") (pin "1") (pinfunction "1_1") (pintype "passive"))
      (node (ref "C42") (pin "1") (pinfunction "1_1") (pintype "passive"))
      (node (ref "D10") (pin "1") (pinfunction "GND_1") (pintype "power_in"))
      (node (ref "D3") (pin "1") (pinfunction "GND_1") (pintype "power_in"))
      (node (ref "D4") (pin "1") (pinfunction "GND_1") (pintype "power_in"))
      (node (ref "D5") (pin "1") (pinfunction "GND_1") (pintype "power_in"))
      (node (ref "D6") (pin "1") (pinfunction "GND_1") (pintype "power_in"))
      (node (ref "D7") (pin "1") (pinfunction "GND_1") (pintype "power_in"))
      (node (ref "D8") (pin "1") (pinfunction "GND_1") (pintype "power_in"))
      (node (ref "D9") (pin "1") (pinfunction "GND_1") (pintype "power_in"))
      (node (ref "J10") (pin "1") (pinfunction "1_1") (pintype "bidirectional"))
      (node (ref "J10") (pin "10") (pinfunction "10_10") (pintype "bidirectional"))
      (node (ref "J10") (pin "13") (pinfunction "13_13") (pintype "bidirectional"))
      (node (ref "J10") (pin "16") (pinfunction "16_16") (pintype "bidirectional"))
      (node (ref "J10") (pin "19") (pinfunction "19_19") (pintype "bidirectional"))
      (node (ref "J10") (pin "22") (pinfunction "22_22") (pintype "bidirectional"))
      (node (ref "J10") (pin "25") (pinfunction "25_25") (pintype "bidirectional"))
      (node (ref "J10") (pin "4") (pinfunction "4_4") (pintype "bidirectional"))
      (node (ref "J10") (pin "7") (pinfunction "7_7") (pintype "bidirectional"))
      (node (ref "J11") (pin "1") (pinfunction "1_1") (pintype "bidirectional"))
      (node (ref "J11") (pin "10") (pinfunction "10_10") (pintype "bidirectional"))
      (node (ref "J11") (pin "13") (pinfunction "13_13") (pintype "bidirectional"))
      (node (ref "J11") (pin "16") (pinfunction "16_16") (pintype "bidirectional"))
      (node (ref "J11") (pin "19") (pinfunction "19_19") (pintype "bidirectional"))
      (node (ref "J11") (pin "22") (pinfunction "22_22") (pintype "bidirectional"))
      (node (ref "J11") (pin "25") (pinfunction "25_25") (pintype "bidirectional"))
      (node (ref "J11") (pin "4") (pinfunction "4_4") (pintype "bidirectional"))
      (node (ref "J11") (pin "7") (pinfunction "7_7") (pintype "bidirectional"))
      (node (ref "J12") (pin "1") (pinfunction "1_1") (pintype "bidirectional"))
      (node (ref "J12") (pin "10") (pinfunction "10_10") (pintype "bidirectional"))
      (node (ref "J12") (pin "13") (pinfunction "13_13") (pintype "bidirectional"))
      (node (ref "J12") (pin "16") (pinfunction "16_16") (pintype "bidirectional"))
      (node (ref "J12") (pin "19") (pinfunction "19_19") (pintype "bidirectional"))
      (node (ref "J12") (pin "22") (pinfunction "22_22") (pintype "bidirectional"))
      (node (ref "J12") (pin "25") (pinfunction "25_25") (pintype "bidirectional"))
      (node (ref "J12") (pin "4") (pinfunction "4_4") (pintype "bidirectional"))
      (node (ref "J12") (pin "7") (pinfunction "7_7") (pintype "bidirectional"))
      (node (ref "J13") (pin "1") (pinfunction "1_1") (pintype "bidirectional"))
      (node (ref "J13") (pin "10") (pinfunction "10_10") (pintype "bidirectional"))
      (node (ref "J13") (pin "13") (pinfunction "13_13") (pintype "bidirectional"))
      (node (ref "J13") (pin "16") (pinfunction "16_16") (pintype "bidirectional"))
      (node (ref "J13") (pin "19") (pinfunction "19_19") (pintype "bidirectional"))
      (node (ref "J13") (pin "22") (pinfunction "22_22") (pintype "bidirectional"))
      (node (ref "J13") (pin "25") (pinfunction "25_25") (pintype "bidirectional"))
      (node (ref "J13") (pin "4") (pinfunction "4_4") (pintype "bidirectional"))
      (node (ref "J13") (pin "7") (pinfunction "7_7") (pintype "bidirectional"))
      (node (ref "J14") (pin "1") (pinfunction "1_1") (pintype "bidirectional"))
      (node (ref "J14") (pin "10") (pinfunction "10_10") (pintype "bidirectional"))
      (node (ref "J14") (pin "13") (pinfunction "13_13") (pintype "bidirectional"))
      (node (ref "J14") (pin "16") (pinfunction "16_16") (pintype "bidirectional"))
      (node (ref "J14") (pin "19") (pinfunction "19_19") (pintype "bidirectional"))
      (node (ref "J14") (pin "22") (pinfunction "22_22") (pintype "bidirectional"))
      (node (ref "J14") (pin "25") (pinfunction "25_25") (pintype "bidirectional"))
      (node (ref "J14") (pin "4") (pinfunction "4_4") (pintype "bidirectional"))
      (node (ref "J14") (pin "7") (pinfunction "7_7") (pintype "bidirectional"))
      (node (ref "J15") (pin "1") (pinfunction "1_1") (pintype "bidirectional"))
      (node (ref "J15") (pin "10") (pinfunction "10_10") (pintype "bidirectional"))
      (node (ref "J15") (pin "13") (pinfunction "13_13") (pintype "bidirectional"))
      (node (ref "J15") (pin "16") (pinfunction "16_16") (pintype "bidirectional"))
      (node (ref "J15") (pin "19") (pinfunction "19_19") (pintype "bidirectional"))
      (node (ref "J15") (pin "22") (pinfunction "22_22") (pintype "bidirectional"))
      (node (ref "J15") (pin "25") (pinfunction "25_25") (pintype "bidirectional"))
      (node (ref "J15") (pin "4") (pinfunction "4_4") (pintype "bidirectional"))
      (node (ref "J15") (pin "7") (pinfunction "7_7") (pintype "bidirectional"))
      (node (ref "J16") (pin "1") (pinfunction "1_1") (pintype "bidirectional"))
      (node (ref "J16") (pin "10") (pinfunction "10_10") (pintype "bidirectional"))
      (node (ref "J16") (pin "13") (pinfunction "13_13") (pintype "bidirectional"))
      (node (ref "J16") (pin "16") (pinfunction "16_16") (pintype "bidirectional"))
      (node (ref "J16") (pin "19") (pinfunction "19_19") (pintype "bidirectional"))
      (node (ref "J16") (pin "22") (pinfunction "22_22") (pintype "bidirectional"))
      (node (ref "J16") (pin "25") (pinfunction "25_25") (pintype "bidirectional"))
      (node (ref "J16") (pin "4") (pinfunction "4_4") (pintype "bidirectional"))
      (node (ref "J16") (pin "7") (pinfunction "7_7") (pintype "bidirectional"))
      (node (ref "J9") (pin "1") (pinfunction "1_1") (pintype "bidirectional"))
      (node (ref "J9") (pin "10") (pinfunction "10_10") (pintype "bidirectional"))
      (node (ref "J9") (pin "13") (pinfunction "13_13") (pintype "bidirectional"))
      (node (ref "J9") (pin "16") (pinfunction "16_16") (pintype "bidirectional"))
      (node (ref "J9") (pin "19") (pinfunction "19_19") (pintype "bidirectional"))
      (node (ref "J9") (pin "22") (pinfunction "22_22") (pintype "bidirectional"))
      (node (ref "J9") (pin "25") (pinfunction "25_25") (pintype "bidirectional"))
      (node (ref "J9") (pin "4") (pinfunction "4_4") (pintype "bidirectional"))
      (node (ref "J9") (pin "7") (pinfunction "7_7") (pintype "bidirectional"))
    )
    (net (code "158") (name "Net-(F1-Pad2)") (class "Default")
      (node (ref "F1") (pin "2") (pinfunction "2_2") (pintype "passive"))
      (node (ref "J10") (pin "30") (pinfunction "30_30") (pintype "bidirectional"))
      (node (ref "J11") (pin "30") (pinfunction "30_30") (pintype "bidirectional"))
      (node (ref "J12") (pin "30") (pinfunction "30_30") (pintype "bidirectional"))
      (node (ref "J9") (pin "30") (pinfunction "30_30") (pintype "bidirectional"))
    )
    (net (code "159") (name "Net-(F2-Pad2)") (class "Default")
      (node (ref "F2") (pin "2") (pinfunction "2_2") (pintype "passive"))
      (node (ref "J13") (pin "30") (pinfunction "30_30") (pintype "bidirectional"))
      (node (ref "J14") (pin "30") (pinfunction "30_30") (pintype "bidirectional"))
      (node (ref "J15") (pin "30") (pinfunction "30_30") (pintype "bidirectional"))
      (node (ref "J16") (pin "30") (pinfunction "30_30") (pintype "bidirectional"))
    )
    (net (code "160") (name "P3V3") (class "Default")
      (node (ref "C30") (pin "2") (pinfunction "2_2") (pintype "passive"))
      (node (ref "C35") (pin "2") (pinfunction "2_2") (pintype "passive"))
      (node (ref "C36") (pin "2") (pinfunction "2_2") (pintype "passive"))
      (node (ref "C37") (pin "2") (pinfunction "2_2") (pintype "passive"))
      (node (ref "C39") (pin "2") (pinfunction "2_2") (pintype "passive"))
      (node (ref "C40") (pin "2") (pinfunction "2_2") (pintype "passive"))
      (node (ref "C41") (pin "2") (pinfunction "2_2") (pintype "passive"))
      (node (ref "C42") (pin "2") (pinfunction "2_2") (pintype "passive"))
      (node (ref "D10") (pin "4") (pinfunction "VCC_4") (pintype "power_in"))
      (node (ref "D3") (pin "4") (pinfunction "VCC_4") (pintype "power_in"))
      (node (ref "D4") (pin "4") (pinfunction "VCC_4") (pintype "power_in"))
      (node (ref "D5") (pin "4") (pinfunction "VCC_4") (pintype "power_in"))
      (node (ref "D6") (pin "4") (pinfunction "VCC_4") (pintype "power_in"))
      (node (ref "D7") (pin "4") (pinfunction "VCC_4") (pintype "power_in"))
      (node (ref "D8") (pin "4") (pinfunction "VCC_4") (pintype "power_in"))
      (node (ref "D9") (pin "4") (pinfunction "VCC_4") (pintype "power_in"))
      (node (ref "F1") (pin "1") (pinfunction "1_1") (pintype "passive"))
      (node (ref "F2") (pin "1") (pinfunction "1_1") (pintype "passive"))
    )
    (net (code "161") (name "P12V0") (class "Default")
      (node (ref "J10") (pin "28") (pinfunction "28_28") (pintype "bidirectional"))
      (node (ref "J10") (pin "29") (pinfunction "29_29") (pintype "bidirectional"))
      (node (ref "J11") (pin "28") (pinfunction "28_28") (pintype "bidirectional"))
      (node (ref "J11") (pin "29") (pinfunction "29_29") (pintype "bidirectional"))
      (node (ref "J12") (pin "28") (pinfunction "28_28") (pintype "bidirectional"))
      (node (ref "J12") (pin "29") (pinfunction "29_29") (pintype "bidirectional"))
      (node (ref "J13") (pin "28") (pinfunction "28_28") (pintype "bidirectional"))
      (node (ref "J13") (pin "29") (pinfunction "29_29") (pintype "bidirectional"))
      (node (ref "J14") (pin "28") (pinfunction "28_28") (pintype "bidirectional"))
      (node (ref "J14") (pin "29") (pinfunction "29_29") (pintype "bidirectional"))
      (node (ref "J15") (pin "28") (pinfunction "28_28") (pintype "bidirectional"))
      (node (ref "J15") (pin "29") (pinfunction "29_29") (pintype "bidirectional"))
      (node (ref "J16") (pin "28") (pinfunction "28_28") (pintype "bidirectional"))
      (node (ref "J16") (pin "29") (pinfunction "29_29") (pintype "bidirectional"))
      (node (ref "J9") (pin "28") (pinfunction "28_28") (pintype "bidirectional"))
      (node (ref "J9") (pin "29") (pinfunction "29_29") (pintype "bidirectional"))
    )
  )
)
